# v1.net
KiCad netlist of a schematic drawn in Altium Designer
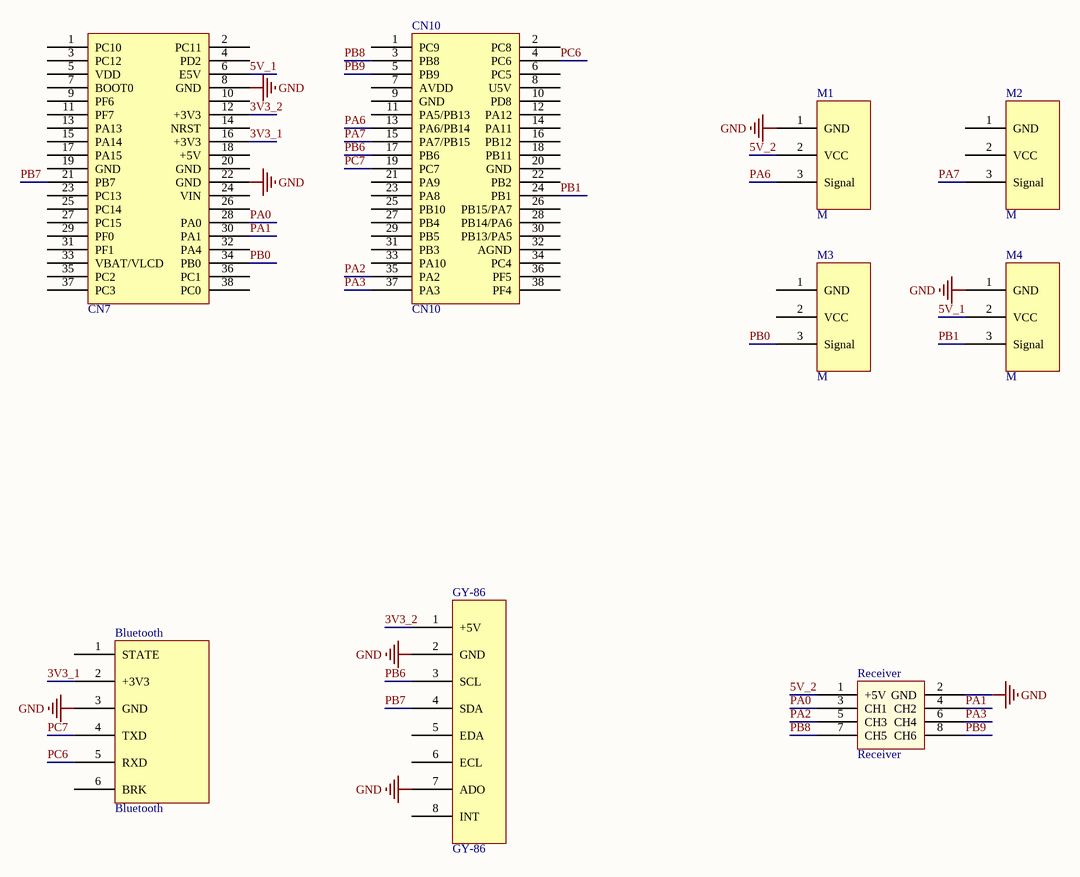
[diagram p0: 转接板v1.SchDoc]

(export (version "E")
  (design (tool "Eeschema 10.0.6"))
  (components
    (comp (ref "Bluetooth")
      (value "Bluetooth")
      (footprint "Bluetooth")
      (libsource (lib "Integrated_Library") (part "Bluetooth"))
    )
    (comp (ref "CN7") (value "CN7") (footprint "CN7") (libsource (lib "Integrated_Library") (part "CN7")))
    (comp (ref "CN10") (value "CN10") (footprint "CN10") (libsource (lib "Integrated_Library") (part "CN10")))
    (comp (ref "GY-86")
      (value "GY-86")
      (footprint "GY-86")
      (libsource (lib "Integrated_Library") (part "GY-86"))
    )
    (comp (ref "M1") (value "M") (footprint "M") (libsource (lib "Integrated_Library") (part "M")))
    (comp (ref "M2") (value "M") (footprint "M") (libsource (lib "Integrated_Library") (part "M")))
    (comp (ref "M3") (value "M") (footprint "M") (libsource (lib "Integrated_Library") (part "M")))
    (comp (ref "M4") (value "M") (footprint "M") (libsource (lib "Integrated_Library") (part "M")))
    (comp (ref "Receiver")
      (value "Receiver")
      (footprint "Receiver")
      (libsource (lib "Integrated_Library") (part "Receiver"))
    )
  )
  (nets
    (net (code "1") (name "/3V3_1") (class "Default")
      (node (ref "Bluetooth") (pin "2") (pinfunction "+3V3_2") (pintype "passive"))
      (node (ref "CN7") (pin "16") (pinfunction "+3V3_16") (pintype "passive"))
    )
    (net (code "2") (name "/3V3_2") (class "Default")
      (node (ref "CN7") (pin "12") (pinfunction "+3V3_12") (pintype "passive"))
      (node (ref "GY-86") (pin "1") (pinfunction "+5V_1") (pintype "passive"))
    )
    (net (code "3") (name "/5V_1") (class "Default")
      (node (ref "CN7") (pin "6") (pinfunction "E5V_6") (pintype "passive"))
      (node (ref "M4") (pin "2") (pinfunction "VCC_2") (pintype "passive"))
    )
    (net (code "4") (name "/5V_2") (class "Default")
      (node (ref "M1") (pin "2") (pinfunction "VCC_2") (pintype "passive"))
      (node (ref "Receiver") (pin "1") (pinfunction "+5V_1") (pintype "passive"))
    )
    (net (code "6") (name "/PA0") (class "Default")
      (node (ref "CN7") (pin "28") (pinfunction "PA0_28") (pintype "passive"))
      (node (ref "Receiver") (pin "3") (pinfunction "CH1_3") (pintype "passive"))
    )
    (net (code "7") (name "/PA1") (class "Default")
      (node (ref "CN7") (pin "30") (pinfunction "PA1_30") (pintype "passive"))
      (node (ref "Receiver") (pin "4") (pinfunction "CH2_4") (pintype "passive"))
    )
    (net (code "8") (name "/PA2") (class "Default")
      (node (ref "CN10") (pin "35") (pinfunction "PA2_35") (pintype "passive"))
      (node (ref "Receiver") (pin "5") (pinfunction "CH3_5") (pintype "passive"))
    )
    (net (code "9") (name "/PA3") (class "Default")
      (node (ref "CN10") (pin "37") (pinfunction "PA3_37") (pintype "passive"))
      (node (ref "Receiver") (pin "6") (pinfunction "CH4_6") (pintype "passive"))
    )
    (net (code "10") (name "/PA6") (class "Default")
      (node (ref "CN10") (pin "13") (pinfunction "PA6/PB14_13") (pintype "passive"))
      (node (ref "M1") (pin "3") (pinfunction "Signal_3") (pintype "passive"))
    )
    (net (code "11") (name "/PA7") (class "Default")
      (node (ref "CN10") (pin "15") (pinfunction "PA7/PB15_15") (pintype "passive"))
      (node (ref "M2") (pin "3") (pinfunction "Signal_3") (pintype "passive"))
    )
    (net (code "12") (name "/PB0") (class "Default")
      (node (ref "CN7") (pin "34") (pinfunction "PB0_34") (pintype "passive"))
      (node (ref "M3") (pin "3") (pinfunction "Signal_3") (pintype "passive"))
    )
    (net (code "13") (name "/PB1") (class "Default")
      (node (ref "CN10") (pin "24") (pinfunction "PB1_24") (pintype "passive"))
      (node (ref "M4") (pin "3") (pinfunction "Signal_3") (pintype "passive"))
    )
    (net (code "14") (name "/PB6") (class "Default")
      (node (ref "CN10") (pin "17") (pinfunction "PB6_17") (pintype "passive"))
      (node (ref "GY-86") (pin "3") (pinfunction "SCL_3") (pintype "passive"))
    )
    (net (code "15") (name "/PB7") (class "Default")
      (node (ref "CN7") (pin "21") (pinfunction "PB7_21") (pintype "passive"))
      (node (ref "GY-86") (pin "4") (pinfunction "SDA_4") (pintype "passive"))
    )
    (net (code "16") (name "/PB8") (class "Default")
      (node (ref "CN10") (pin "3") (pinfunction "PB8_3") (pintype "passive"))
      (node (ref "Receiver") (pin "7") (pinfunction "CH5_7") (pintype "passive"))
    )
    (net (code "17") (name "/PB9") (class "Default")
      (node (ref "CN10") (pin "5") (pinfunction "PB9_5") (pintype "passive"))
      (node (ref "Receiver") (pin "8") (pinfunction "CH6_8") (pintype "passive"))
    )
    (net (code "18") (name "/PC6") (class "Default")
      (node (ref "Bluetooth") (pin "5") (pinfunction "RXD_5") (pintype "passive"))
      (node (ref "CN10") (pin "4") (pinfunction "PC6_4") (pintype "passive"))
    )
    (net (code "19") (name "/PC7") (class "Default")
      (node (ref "Bluetooth") (pin "4") (pinfunction "TXD_4") (pintype "passive"))
      (node (ref "CN10") (pin "19") (pinfunction "PC7_19") (pintype "passive"))
    )
    (net (code "20") (name "GND") (class "Default")
      (node (ref "Bluetooth") (pin "3") (pinfunction "GND_3") (pintype "passive"))
      (node (ref "CN7") (pin "22") (pinfunction "GND_22") (pintype "passive"))
      (node (ref "CN7") (pin "8") (pinfunction "GND_8") (pintype "passive"))
      (node (ref "GY-86") (pin "2") (pinfunction "GND_2") (pintype "passive"))
      (node (ref "GY-86") (pin "7") (pinfunction "ADO_7") (pintype "passive"))
      (node (ref "M1") (pin "1") (pinfunction "GND_1") (pintype "passive"))
      (node (ref "M4") (pin "1") (pinfunction "GND_1") (pintype "passive"))
      (node (ref "Receiver") (pin "2") (pinfunction "GND_2") (pintype "passive"))
    )
    (net (code "21") (name "unconnected-(Bluetooth-BRK-Pad6)") (class "Default")
      (node (ref "Bluetooth") (pin "6") (pinfunction "BRK_6") (pintype "passive"))
    )
    (net (code "22") (name "unconnected-(Bluetooth-STATE-Pad1)") (class "Default")
      (node (ref "Bluetooth") (pin "1") (pinfunction "STATE_1") (pintype "passive"))
    )
    (net (code "23") (name "unconnected-(CN7-+5V-Pad18)") (class "Default")
      (node (ref "CN7") (pin "18") (pinfunction "+5V_18") (pintype "passive"))
    )
    (net (code "24") (name "unconnected-(CN7-BOOT0-Pad7)") (class "Default")
      (node (ref "CN7") (pin "7") (pinfunction "BOOT0_7") (pintype "passive"))
    )
    (net (code "25") (name "unconnected-(CN7-GND-Pad19)") (class "Default")
      (node (ref "CN7") (pin "19") (pinfunction "GND_19") (pintype "passive"))
    )
    (net (code "26") (name "unconnected-(CN7-GND-Pad20)") (class "Default")
      (node (ref "CN7") (pin "20") (pinfunction "GND_20") (pintype "passive"))
    )
    (net (code "27") (name "unconnected-(CN7-NRST-Pad14)") (class "Default")
      (node (ref "CN7") (pin "14") (pinfunction "NRST_14") (pintype "passive"))
    )
    (net (code "28") (name "unconnected-(CN7-PA4-Pad32)") (class "Default")
      (node (ref "CN7") (pin "32") (pinfunction "PA4_32") (pintype "passive"))
    )
    (net (code "29") (name "unconnected-(CN7-PA13-Pad13)") (class "Default")
      (node (ref "CN7") (pin "13") (pinfunction "PA13_13") (pintype "passive"))
    )
    (net (code "30") (name "unconnected-(CN7-PA14-Pad15)") (class "Default")
      (node (ref "CN7") (pin "15") (pinfunction "PA14_15") (pintype "passive"))
    )
    (net (code "31") (name "unconnected-(CN7-PA15-Pad17)") (class "Default")
      (node (ref "CN7") (pin "17") (pinfunction "PA15_17") (pintype "passive"))
    )
    (net (code "32") (name "unconnected-(CN7-PC0-Pad38)") (class "Default")
      (node (ref "CN7") (pin "38") (pinfunction "PC0_38") (pintype "passive"))
    )
    (net (code "33") (name "unconnected-(CN7-PC1-Pad36)") (class "Default")
      (node (ref "CN7") (pin "36") (pinfunction "PC1_36") (pintype "passive"))
    )
    (net (code "34") (name "unconnected-(CN7-PC2-Pad35)") (class "Default")
      (node (ref "CN7") (pin "35") (pinfunction "PC2_35") (pintype "passive"))
    )
    (net (code "35") (name "unconnected-(CN7-PC3-Pad37)") (class "Default")
      (node (ref "CN7") (pin "37") (pinfunction "PC3_37") (pintype "passive"))
    )
    (net (code "36") (name "unconnected-(CN7-PC10-Pad1)") (class "Default")
      (node (ref "CN7") (pin "1") (pinfunction "PC10_1") (pintype "passive"))
    )
    (net (code "37") (name "unconnected-(CN7-PC11-Pad2)") (class "Default")
      (node (ref "CN7") (pin "2") (pinfunction "PC11_2") (pintype "passive"))
    )
    (net (code "38") (name "unconnected-(CN7-PC12-Pad3)") (class "Default")
      (node (ref "CN7") (pin "3") (pinfunction "PC12_3") (pintype "passive"))
    )
    (net (code "39") (name "unconnected-(CN7-PC13-Pad23)") (class "Default")
      (node (ref "CN7") (pin "23") (pinfunction "PC13_23") (pintype "passive"))
    )
    (net (code "40") (name "unconnected-(CN7-PC14-Pad25)") (class "Default")
      (node (ref "CN7") (pin "25") (pinfunction "PC14_25") (pintype "passive"))
    )
    (net (code "41") (name "unconnected-(CN7-PC15-Pad27)") (class "Default")
      (node (ref "CN7") (pin "27") (pinfunction "PC15_27") (pintype "passive"))
    )
    (net (code "42") (name "unconnected-(CN7-PD2-Pad4)") (class "Default")
      (node (ref "CN7") (pin "4") (pinfunction "PD2_4") (pintype "passive"))
    )
    (net (code "43") (name "unconnected-(CN7-PF0-Pad29)") (class "Default")
      (node (ref "CN7") (pin "29") (pinfunction "PF0_29") (pintype "passive"))
    )
    (net (code "44") (name "unconnected-(CN7-PF1-Pad31)") (class "Default")
      (node (ref "CN7") (pin "31") (pinfunction "PF1_31") (pintype "passive"))
    )
    (net (code "45") (name "unconnected-(CN7-PF6-Pad9)") (class "Default")
      (node (ref "CN7") (pin "9") (pinfunction "PF6_9") (pintype "passive"))
    )
    (net (code "46") (name "unconnected-(CN7-PF7-Pad11)") (class "Default")
      (node (ref "CN7") (pin "11") (pinfunction "PF7_11") (pintype "passive"))
    )
    (net (code "47") (name "unconnected-(CN7-Pad10)") (class "Default")
      (node (ref "CN7") (pin "10") (pintype "passive"))
    )
    (net (code "48") (name "unconnected-(CN7-Pad26)") (class "Default")
      (node (ref "CN7") (pin "26") (pintype "passive"))
    )
    (net (code "49") (name "unconnected-(CN7-VBAT{slash}VLCD-Pad33)") (class "Default")
      (node (ref "CN7") (pin "33") (pinfunction "VBAT/VLCD_33") (pintype "passive"))
    )
    (net (code "50") (name "unconnected-(CN7-VDD-Pad5)") (class "Default")
      (node (ref "CN7") (pin "5") (pinfunction "VDD_5") (pintype "passive"))
    )
    (net (code "51") (name "unconnected-(CN7-VIN-Pad24)") (class "Default")
      (node (ref "CN7") (pin "24") (pinfunction "VIN_24") (pintype "passive"))
    )
    (net (code "52") (name "unconnected-(CN10-AGND-Pad32)") (class "Default")
      (node (ref "CN10") (pin "32") (pinfunction "AGND_32") (pintype "passive"))
    )
    (net (code "53") (name "unconnected-(CN10-AVDD-Pad7)") (class "Default")
      (node (ref "CN10") (pin "7") (pinfunction "AVDD_7") (pintype "passive"))
    )
    (net (code "54") (name "unconnected-(CN10-GND-Pad9)") (class "Default")
      (node (ref "CN10") (pin "9") (pinfunction "GND_9") (pintype "passive"))
    )
    (net (code "55") (name "unconnected-(CN10-GND-Pad20)") (class "Default")
      (node (ref "CN10") (pin "20") (pinfunction "GND_20") (pintype "passive"))
    )
    (net (code "56") (name "unconnected-(CN10-PA5{slash}PB13-Pad11)") (class "Default")
      (node (ref "CN10") (pin "11") (pinfunction "PA5/PB13_11") (pintype "passive"))
    )
    (net (code "57") (name "unconnected-(CN10-PA8-Pad23)") (class "Default")
      (node (ref "CN10") (pin "23") (pinfunction "PA8_23") (pintype "passive"))
    )
    (net (code "58") (name "unconnected-(CN10-PA9-Pad21)") (class "Default")
      (node (ref "CN10") (pin "21") (pinfunction "PA9_21") (pintype "passive"))
    )
    (net (code "59") (name "unconnected-(CN10-PA10-Pad33)") (class "Default")
      (node (ref "CN10") (pin "33") (pinfunction "PA10_33") (pintype "passive"))
    )
    (net (code "60") (name "unconnected-(CN10-PA11-Pad14)") (class "Default")
      (node (ref "CN10") (pin "14") (pinfunction "PA11_14") (pintype "passive"))
    )
    (net (code "61") (name "unconnected-(CN10-PA12-Pad12)") (class "Default")
      (node (ref "CN10") (pin "12") (pinfunction "PA12_12") (pintype "passive"))
    )
    (net (code "62") (name "unconnected-(CN10-PB2-Pad22)") (class "Default")
      (node (ref "CN10") (pin "22") (pinfunction "PB2_22") (pintype "passive"))
    )
    (net (code "63") (name "unconnected-(CN10-PB3-Pad31)") (class "Default")
      (node (ref "CN10") (pin "31") (pinfunction "PB3_31") (pintype "passive"))
    )
    (net (code "64") (name "unconnected-(CN10-PB4-Pad27)") (class "Default")
      (node (ref "CN10") (pin "27") (pinfunction "PB4_27") (pintype "passive"))
    )
    (net (code "65") (name "unconnected-(CN10-PB5-Pad29)") (class "Default")
      (node (ref "CN10") (pin "29") (pinfunction "PB5_29") (pintype "passive"))
    )
    (net (code "66") (name "unconnected-(CN10-PB10-Pad25)") (class "Default")
      (node (ref "CN10") (pin "25") (pinfunction "PB10_25") (pintype "passive"))
    )
    (net (code "67") (name "unconnected-(CN10-PB11-Pad18)") (class "Default")
      (node (ref "CN10") (pin "18") (pinfunction "PB11_18") (pintype "passive"))
    )
    (net (code "68") (name "unconnected-(CN10-PB12-Pad16)") (class "Default")
      (node (ref "CN10") (pin "16") (pinfunction "PB12_16") (pintype "passive"))
    )
    (net (code "69") (name "unconnected-(CN10-PB13{slash}PA5-Pad30)") (class "Default")
      (node (ref "CN10") (pin "30") (pinfunction "PB13/PA5_30") (pintype "passive"))
    )
    (net (code "70") (name "unconnected-(CN10-PB14{slash}PA6-Pad28)") (class "Default")
      (node (ref "CN10") (pin "28") (pinfunction "PB14/PA6_28") (pintype "passive"))
    )
    (net (code "71") (name "unconnected-(CN10-PB15{slash}PA7-Pad26)") (class "Default")
      (node (ref "CN10") (pin "26") (pinfunction "PB15/PA7_26") (pintype "passive"))
    )
    (net (code "72") (name "unconnected-(CN10-PC4-Pad34)") (class "Default")
      (node (ref "CN10") (pin "34") (pinfunction "PC4_34") (pintype "passive"))
    )
    (net (code "73") (name "unconnected-(CN10-PC5-Pad6)") (class "Default")
      (node (ref "CN10") (pin "6") (pinfunction "PC5_6") (pintype "passive"))
    )
    (net (code "74") (name "unconnected-(CN10-PC8-Pad2)") (class "Default")
      (node (ref "CN10") (pin "2") (pinfunction "PC8_2") (pintype "passive"))
    )
    (net (code "75") (name "unconnected-(CN10-PC9-Pad1)") (class "Default")
      (node (ref "CN10") (pin "1") (pinfunction "PC9_1") (pintype "passive"))
    )
    (net (code "76") (name "unconnected-(CN10-PD8-Pad10)") (class "Default")
      (node (ref "CN10") (pin "10") (pinfunction "PD8_10") (pintype "passive"))
    )
    (net (code "77") (name "unconnected-(CN10-PF4-Pad38)") (class "Default")
      (node (ref "CN10") (pin "38") (pinfunction "PF4_38") (pintype "passive"))
    )
    (net (code "78") (name "unconnected-(CN10-PF5-Pad36)") (class "Default")
      (node (ref "CN10") (pin "36") (pinfunction "PF5_36") (pintype "passive"))
    )
    (net (code "79") (name "unconnected-(CN10-U5V-Pad8)") (class "Default")
      (node (ref "CN10") (pin "8") (pinfunction "U5V_8") (pintype "passive"))
    )
    (net (code "80") (name "unconnected-(GY-86-ECL-Pad6)") (class "Default")
      (node (ref "GY-86") (pin "6") (pinfunction "ECL_6") (pintype "passive"))
    )
    (net (code "81") (name "unconnected-(GY-86-EDA-Pad5)") (class "Default")
      (node (ref "GY-86") (pin "5") (pinfunction "EDA_5") (pintype "passive"))
    )
    (net (code "82") (name "unconnected-(GY-86-INT-Pad8)") (class "Default")
      (node (ref "GY-86") (pin "8") (pinfunction "INT_8") (pintype "passive"))
    )
    (net (code "83") (name "unconnected-(M2-GND-Pad1)") (class "Default")
      (node (ref "M2") (pin "1") (pinfunction "GND_1") (pintype "passive"))
    )
    (net (code "84") (name "unconnected-(M2-VCC-Pad2)") (class "Default")
      (node (ref "M2") (pin "2") (pinfunction "VCC_2") (pintype "passive"))
    )
    (net (code "85") (name "unconnected-(M3-GND-Pad1)") (class "Default")
      (node (ref "M3") (pin "1") (pinfunction "GND_1") (pintype "passive"))
    )
    (net (code "86") (name "unconnected-(M3-VCC-Pad2)") (class "Default")
      (node (ref "M3") (pin "2") (pinfunction "VCC_2") (pintype "passive"))
    )
  )
)
